# dynalo-dac.net
KiCad netlist of a schematic drawn in EAGLE
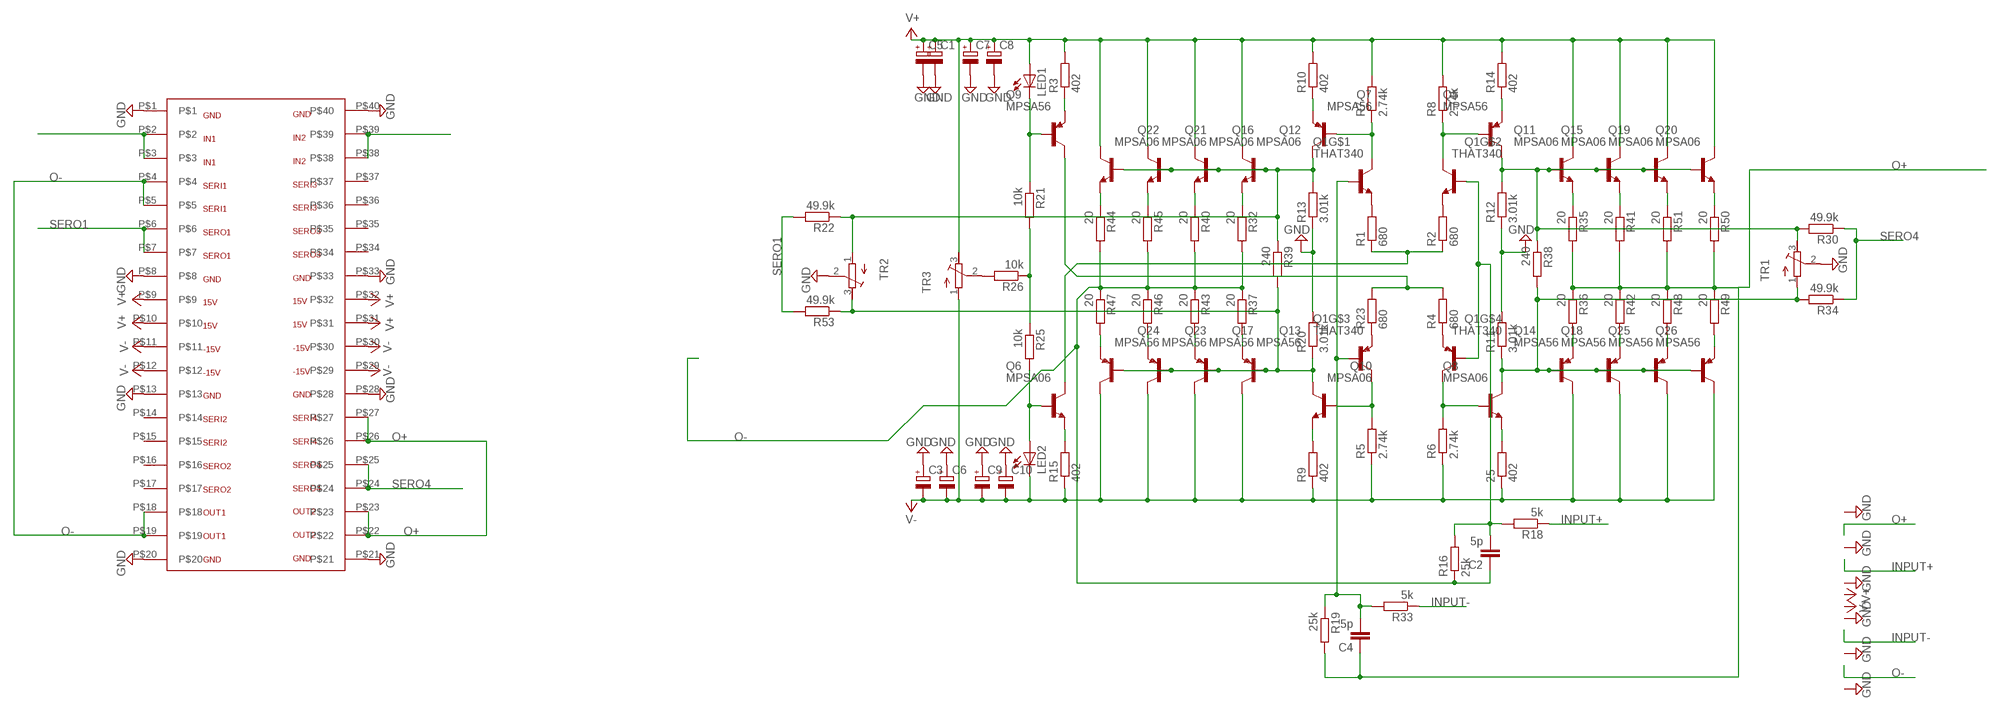
[diagram p0: schematic, sheet 1]

(export (version "E")
  (design (tool "Eeschema 10.0.6"))
  (components
    (comp (ref "25")
      (value "402")
      (footprint "eagle-import:MINI_MELF-0204W")
      (libsource (lib "eagle-import") (part "R-EU_MELF0204W"))
    )
    (comp (ref "C1")
      (value "CPOL-EUSP-CAP-CX")
      (footprint "eagle-import:SP-CAP-CX")
      (libsource (lib "eagle-import") (part "CPOL-EUSP-CAP-CX"))
    )
    (comp (ref "C2")
      (value "5p")
      (footprint "eagle-import:C0805")
      (libsource (lib "eagle-import") (part "C-EUC0805"))
    )
    (comp (ref "C3")
      (value "CPOL-EUSP-CAP-CX")
      (footprint "eagle-import:SP-CAP-CX")
      (libsource (lib "eagle-import") (part "CPOL-EUSP-CAP-CX"))
    )
    (comp (ref "C4")
      (value "5p")
      (footprint "eagle-import:C0805")
      (libsource (lib "eagle-import") (part "C-EUC0805"))
    )
    (comp (ref "C5")
      (value "CPOL-EUSP-CAP-CX")
      (footprint "eagle-import:SP-CAP-CX")
      (libsource (lib "eagle-import") (part "CPOL-EUSP-CAP-CX"))
    )
    (comp (ref "C6")
      (value "CPOL-EUSP-CAP-CX")
      (footprint "eagle-import:SP-CAP-CX")
      (libsource (lib "eagle-import") (part "CPOL-EUSP-CAP-CX"))
    )
    (comp (ref "C7")
      (value "CPOL-EUSP-CAP-CX")
      (footprint "eagle-import:SP-CAP-CX")
      (libsource (lib "eagle-import") (part "CPOL-EUSP-CAP-CX"))
    )
    (comp (ref "C8")
      (value "CPOL-EUSP-CAP-CX")
      (footprint "eagle-import:SP-CAP-CX")
      (libsource (lib "eagle-import") (part "CPOL-EUSP-CAP-CX"))
    )
    (comp (ref "C9")
      (value "CPOL-EUSP-CAP-CX")
      (footprint "eagle-import:SP-CAP-CX")
      (libsource (lib "eagle-import") (part "CPOL-EUSP-CAP-CX"))
    )
    (comp (ref "C10")
      (value "CPOL-EUSP-CAP-CX")
      (footprint "eagle-import:SP-CAP-CX")
      (libsource (lib "eagle-import") (part "CPOL-EUSP-CAP-CX"))
    )
    (comp (ref "LED1")
      (value "LED5MM")
      (footprint "eagle-import:LED5MM")
      (libsource (lib "eagle-import") (part "LED5MM"))
    )
    (comp (ref "LED2")
      (value "LED5MM")
      (footprint "eagle-import:LED5MM")
      (libsource (lib "eagle-import") (part "LED5MM"))
    )
    (comp (ref "Q1")
      (value "THAT340")
      (footprint "eagle-import:DIP254P762X510-14")
      (libsource (lib "eagle-import") (part "THAT340"))
    )
    (comp (ref "Q5")
      (value "MPSA56")
      (footprint "eagle-import:TO92-BCE")
      (libsource (lib "eagle-import") (part "MPSA56"))
    )
    (comp (ref "Q6")
      (value "MPSA06")
      (footprint "eagle-import:TO92-1")
      (libsource (lib "eagle-import") (part "MPSA06"))
    )
    (comp (ref "Q7")
      (value "MPSA56")
      (footprint "eagle-import:TO92-BCE")
      (libsource (lib "eagle-import") (part "MPSA56"))
    )
    (comp (ref "Q8")
      (value "MPSA06")
      (footprint "eagle-import:TO92-1")
      (libsource (lib "eagle-import") (part "MPSA06"))
    )
    (comp (ref "Q9")
      (value "MPSA56")
      (footprint "eagle-import:TO92-BCE")
      (libsource (lib "eagle-import") (part "MPSA56"))
    )
    (comp (ref "Q10")
      (value "MPSA06")
      (footprint "eagle-import:TO92-1")
      (libsource (lib "eagle-import") (part "MPSA06"))
    )
    (comp (ref "Q11")
      (value "MPSA06")
      (footprint "eagle-import:TO92-1")
      (libsource (lib "eagle-import") (part "MPSA06"))
    )
    (comp (ref "Q12")
      (value "MPSA06")
      (footprint "eagle-import:TO92-1")
      (libsource (lib "eagle-import") (part "MPSA06"))
    )
    (comp (ref "Q13")
      (value "MPSA56")
      (footprint "eagle-import:TO92-BCE")
      (libsource (lib "eagle-import") (part "MPSA56"))
    )
    (comp (ref "Q14")
      (value "MPSA56")
      (footprint "eagle-import:TO92-BCE")
      (libsource (lib "eagle-import") (part "MPSA56"))
    )
    (comp (ref "Q15")
      (value "MPSA06")
      (footprint "eagle-import:TO92-1")
      (libsource (lib "eagle-import") (part "MPSA06"))
    )
    (comp (ref "Q16")
      (value "MPSA06")
      (footprint "eagle-import:TO92-1")
      (libsource (lib "eagle-import") (part "MPSA06"))
    )
    (comp (ref "Q17")
      (value "MPSA56")
      (footprint "eagle-import:TO92-BCE")
      (libsource (lib "eagle-import") (part "MPSA56"))
    )
    (comp (ref "Q18")
      (value "MPSA56")
      (footprint "eagle-import:TO92-BCE")
      (libsource (lib "eagle-import") (part "MPSA56"))
    )
    (comp (ref "Q19")
      (value "MPSA06")
      (footprint "eagle-import:TO92-1")
      (libsource (lib "eagle-import") (part "MPSA06"))
    )
    (comp (ref "Q20")
      (value "MPSA06")
      (footprint "eagle-import:TO92-1")
      (libsource (lib "eagle-import") (part "MPSA06"))
    )
    (comp (ref "Q21")
      (value "MPSA06")
      (footprint "eagle-import:TO92-1")
      (libsource (lib "eagle-import") (part "MPSA06"))
    )
    (comp (ref "Q22")
      (value "MPSA06")
      (footprint "eagle-import:TO92-1")
      (libsource (lib "eagle-import") (part "MPSA06"))
    )
    (comp (ref "Q23")
      (value "MPSA56")
      (footprint "eagle-import:TO92-BCE")
      (libsource (lib "eagle-import") (part "MPSA56"))
    )
    (comp (ref "Q24")
      (value "MPSA56")
      (footprint "eagle-import:TO92-BCE")
      (libsource (lib "eagle-import") (part "MPSA56"))
    )
    (comp (ref "Q25")
      (value "MPSA56")
      (footprint "eagle-import:TO92-BCE")
      (libsource (lib "eagle-import") (part "MPSA56"))
    )
    (comp (ref "Q26")
      (value "MPSA56")
      (footprint "eagle-import:TO92-BCE")
      (libsource (lib "eagle-import") (part "MPSA56"))
    )
    (comp (ref "R1")
      (value "680")
      (footprint "eagle-import:MINI_MELF-0204W")
      (libsource (lib "eagle-import") (part "R-EU_MELF0204W"))
    )
    (comp (ref "R2")
      (value "680")
      (footprint "eagle-import:MINI_MELF-0204W")
      (libsource (lib "eagle-import") (part "R-EU_MELF0204W"))
    )
    (comp (ref "R3")
      (value "402")
      (footprint "eagle-import:MINI_MELF-0204W")
      (libsource (lib "eagle-import") (part "R-EU_MELF0204W"))
    )
    (comp (ref "R4")
      (value "680")
      (footprint "eagle-import:MINI_MELF-0204W")
      (libsource (lib "eagle-import") (part "R-EU_MELF0204W"))
    )
    (comp (ref "R5")
      (value "2.74k")
      (footprint "eagle-import:MINI_MELF-0204W")
      (libsource (lib "eagle-import") (part "R-EU_MELF0204W"))
    )
    (comp (ref "R6")
      (value "2.74k")
      (footprint "eagle-import:MINI_MELF-0204W")
      (libsource (lib "eagle-import") (part "R-EU_MELF0204W"))
    )
    (comp (ref "R7")
      (value "2.74k")
      (footprint "eagle-import:MINI_MELF-0204W")
      (libsource (lib "eagle-import") (part "R-EU_MELF0204W"))
    )
    (comp (ref "R8")
      (value "2.74k")
      (footprint "eagle-import:MINI_MELF-0204W")
      (libsource (lib "eagle-import") (part "R-EU_MELF0204W"))
    )
    (comp (ref "R9")
      (value "402")
      (footprint "eagle-import:MINI_MELF-0204W")
      (libsource (lib "eagle-import") (part "R-EU_MELF0204W"))
    )
    (comp (ref "R10")
      (value "402")
      (footprint "eagle-import:MINI_MELF-0204W")
      (libsource (lib "eagle-import") (part "R-EU_MELF0204W"))
    )
    (comp (ref "R11")
      (value "3.01k")
      (footprint "eagle-import:MINI_MELF-0204W")
      (libsource (lib "eagle-import") (part "R-EU_MELF0204W"))
    )
    (comp (ref "R12")
      (value "3.01k")
      (footprint "eagle-import:MINI_MELF-0204W")
      (libsource (lib "eagle-import") (part "R-EU_MELF0204W"))
    )
    (comp (ref "R13")
      (value "3.01k")
      (footprint "eagle-import:MINI_MELF-0204W")
      (libsource (lib "eagle-import") (part "R-EU_MELF0204W"))
    )
    (comp (ref "R14")
      (value "402")
      (footprint "eagle-import:MINI_MELF-0204W")
      (libsource (lib "eagle-import") (part "R-EU_MELF0204W"))
    )
    (comp (ref "R15")
      (value "402")
      (footprint "eagle-import:MINI_MELF-0204W")
      (libsource (lib "eagle-import") (part "R-EU_MELF0204W"))
    )
    (comp (ref "R16")
      (value "25k")
      (footprint "eagle-import:MINI_MELF-0204W")
      (libsource (lib "eagle-import") (part "R-EU_MELF0204W"))
    )
    (comp (ref "R18")
      (value "5k")
      (footprint "eagle-import:MINI_MELF-0204W")
      (libsource (lib "eagle-import") (part "R-EU_MELF0204W"))
    )
    (comp (ref "R19")
      (value "25k")
      (footprint "eagle-import:MINI_MELF-0204W")
      (libsource (lib "eagle-import") (part "R-EU_MELF0204W"))
    )
    (comp (ref "R20")
      (value "3.01k")
      (footprint "eagle-import:MINI_MELF-0204W")
      (libsource (lib "eagle-import") (part "R-EU_MELF0204W"))
    )
    (comp (ref "R21")
      (value "10k")
      (footprint "eagle-import:MINI_MELF-0204W")
      (libsource (lib "eagle-import") (part "R-EU_MELF0204W"))
    )
    (comp (ref "R22")
      (value "49.9k")
      (footprint "eagle-import:MINI_MELF-0204W")
      (libsource (lib "eagle-import") (part "R-EU_MELF0204W"))
    )
    (comp (ref "R23")
      (value "680")
      (footprint "eagle-import:MINI_MELF-0204W")
      (libsource (lib "eagle-import") (part "R-EU_MELF0204W"))
    )
    (comp (ref "R25")
      (value "10k")
      (footprint "eagle-import:MINI_MELF-0204W")
      (libsource (lib "eagle-import") (part "R-EU_MELF0204W"))
    )
    (comp (ref "R26")
      (value "10k")
      (footprint "eagle-import:MINI_MELF-0204W")
      (libsource (lib "eagle-import") (part "R-EU_MELF0204W"))
    )
    (comp (ref "R30")
      (value "49.9k")
      (footprint "eagle-import:MINI_MELF-0204W")
      (libsource (lib "eagle-import") (part "R-EU_MELF0204W"))
    )
    (comp (ref "R32")
      (value "20")
      (footprint "eagle-import:MINI_MELF-0204W")
      (libsource (lib "eagle-import") (part "R-EU_MELF0204W"))
    )
    (comp (ref "R33")
      (value "5k")
      (footprint "eagle-import:MINI_MELF-0204W")
      (libsource (lib "eagle-import") (part "R-EU_MELF0204W"))
    )
    (comp (ref "R34")
      (value "49.9k")
      (footprint "eagle-import:MINI_MELF-0204W")
      (libsource (lib "eagle-import") (part "R-EU_MELF0204W"))
    )
    (comp (ref "R35")
      (value "20")
      (footprint "eagle-import:MINI_MELF-0204W")
      (libsource (lib "eagle-import") (part "R-EU_MELF0204W"))
    )
    (comp (ref "R36")
      (value "20")
      (footprint "eagle-import:MINI_MELF-0204W")
      (libsource (lib "eagle-import") (part "R-EU_MELF0204W"))
    )
    (comp (ref "R37")
      (value "20")
      (footprint "eagle-import:MINI_MELF-0204W")
      (libsource (lib "eagle-import") (part "R-EU_MELF0204W"))
    )
    (comp (ref "R38")
      (value "240")
      (footprint "eagle-import:MINI_MELF-0204W")
      (libsource (lib "eagle-import") (part "R-EU_MELF0204W"))
    )
    (comp (ref "R39")
      (value "240")
      (footprint "eagle-import:MINI_MELF-0204W")
      (libsource (lib "eagle-import") (part "R-EU_MELF0204W"))
    )
    (comp (ref "R40")
      (value "20")
      (footprint "eagle-import:MINI_MELF-0204W")
      (libsource (lib "eagle-import") (part "R-EU_MELF0204W"))
    )
    (comp (ref "R41")
      (value "20")
      (footprint "eagle-import:MINI_MELF-0204W")
      (libsource (lib "eagle-import") (part "R-EU_MELF0204W"))
    )
    (comp (ref "R42")
      (value "20")
      (footprint "eagle-import:MINI_MELF-0204W")
      (libsource (lib "eagle-import") (part "R-EU_MELF0204W"))
    )
    (comp (ref "R43")
      (value "20")
      (footprint "eagle-import:MINI_MELF-0204W")
      (libsource (lib "eagle-import") (part "R-EU_MELF0204W"))
    )
    (comp (ref "R44")
      (value "20")
      (footprint "eagle-import:MINI_MELF-0204W")
      (libsource (lib "eagle-import") (part "R-EU_MELF0204W"))
    )
    (comp (ref "R45")
      (value "20")
      (footprint "eagle-import:MINI_MELF-0204W")
      (libsource (lib "eagle-import") (part "R-EU_MELF0204W"))
    )
    (comp (ref "R46")
      (value "20")
      (footprint "eagle-import:MINI_MELF-0204W")
      (libsource (lib "eagle-import") (part "R-EU_MELF0204W"))
    )
    (comp (ref "R47")
      (value "20")
      (footprint "eagle-import:MINI_MELF-0204W")
      (libsource (lib "eagle-import") (part "R-EU_MELF0204W"))
    )
    (comp (ref "R48")
      (value "20")
      (footprint "eagle-import:MINI_MELF-0204W")
      (libsource (lib "eagle-import") (part "R-EU_MELF0204W"))
    )
    (comp (ref "R49")
      (value "20")
      (footprint "eagle-import:MINI_MELF-0204W")
      (libsource (lib "eagle-import") (part "R-EU_MELF0204W"))
    )
    (comp (ref "R50")
      (value "20")
      (footprint "eagle-import:MINI_MELF-0204W")
      (libsource (lib "eagle-import") (part "R-EU_MELF0204W"))
    )
    (comp (ref "R51")
      (value "20")
      (footprint "eagle-import:MINI_MELF-0204W")
      (libsource (lib "eagle-import") (part "R-EU_MELF0204W"))
    )
    (comp (ref "R53")
      (value "49.9k")
      (footprint "eagle-import:MINI_MELF-0204W")
      (libsource (lib "eagle-import") (part "R-EU_MELF0204W"))
    )
    (comp (ref "TR1")
      (value "R-TRIMM3296W")
      (footprint "eagle-import:RTRIM3296W")
      (libsource (lib "eagle-import") (part "R-TRIMM3296W"))
    )
    (comp (ref "TR2")
      (value "R-TRIMM3296W")
      (footprint "eagle-import:RTRIM3296W")
      (libsource (lib "eagle-import") (part "R-TRIMM3296W"))
    )
    (comp (ref "TR3")
      (value "R-TRIMM3296W")
      (footprint "eagle-import:RTRIM3296W")
      (libsource (lib "eagle-import") (part "R-TRIMM3296W"))
    )
    (comp (ref "U$1")
      (value "VDACA")
      (footprint "eagle-import:VDACA")
      (libsource (lib "eagle-import") (part "VDACA"))
    )
  )
  (nets
    (net (code "1") (name "/INPUT+") (class "Default")
      (node (ref "R18") (pin "1") (pinfunction "1_1") (pintype "passive"))
      (node (ref "U$1") (pin "P$38") (pinfunction "P$38_P$38") (pintype "bidirectional"))
      (node (ref "U$1") (pin "P$39") (pinfunction "P$39_P$39") (pintype "bidirectional"))
    )
    (net (code "2") (name "/INPUT-") (class "Default")
      (node (ref "R33") (pin "1") (pinfunction "1_1") (pintype "passive"))
      (node (ref "U$1") (pin "P$2") (pinfunction "P$2_P$2") (pintype "bidirectional"))
      (node (ref "U$1") (pin "P$3") (pinfunction "P$3_P$3") (pintype "bidirectional"))
    )
    (net (code "3") (name "/O+") (class "Default")
      (node (ref "C4") (pin "1") (pinfunction "1_1") (pintype "passive"))
      (node (ref "R19") (pin "2") (pinfunction "2_2") (pintype "passive"))
      (node (ref "R35") (pin "2") (pinfunction "2_2") (pintype "passive"))
      (node (ref "R36") (pin "1") (pinfunction "1_1") (pintype "passive"))
      (node (ref "R41") (pin "2") (pinfunction "2_2") (pintype "passive"))
      (node (ref "R42") (pin "1") (pinfunction "1_1") (pintype "passive"))
      (node (ref "R48") (pin "1") (pinfunction "1_1") (pintype "passive"))
      (node (ref "R49") (pin "1") (pinfunction "1_1") (pintype "passive"))
      (node (ref "R50") (pin "2") (pinfunction "2_2") (pintype "passive"))
      (node (ref "R51") (pin "2") (pinfunction "2_2") (pintype "passive"))
      (node (ref "U$1") (pin "P$22") (pinfunction "P$22_P$22") (pintype "bidirectional"))
      (node (ref "U$1") (pin "P$23") (pinfunction "P$23_P$23") (pintype "bidirectional"))
      (node (ref "U$1") (pin "P$26") (pinfunction "P$26_P$26") (pintype "bidirectional"))
      (node (ref "U$1") (pin "P$27") (pinfunction "P$27_P$27") (pintype "bidirectional"))
    )
    (net (code "4") (name "/O-") (class "Default")
      (node (ref "C2") (pin "1") (pinfunction "1_1") (pintype "passive"))
      (node (ref "R16") (pin "1") (pinfunction "1_1") (pintype "passive"))
      (node (ref "R32") (pin "2") (pinfunction "2_2") (pintype "passive"))
      (node (ref "R37") (pin "1") (pinfunction "1_1") (pintype "passive"))
      (node (ref "R40") (pin "2") (pinfunction "2_2") (pintype "passive"))
      (node (ref "R43") (pin "1") (pinfunction "1_1") (pintype "passive"))
      (node (ref "R44") (pin "2") (pinfunction "2_2") (pintype "passive"))
      (node (ref "R45") (pin "2") (pinfunction "2_2") (pintype "passive"))
      (node (ref "R46") (pin "1") (pinfunction "1_1") (pintype "passive"))
      (node (ref "R47") (pin "1") (pinfunction "1_1") (pintype "passive"))
      (node (ref "U$1") (pin "P$18") (pinfunction "P$18_P$18") (pintype "bidirectional"))
      (node (ref "U$1") (pin "P$19") (pinfunction "P$19_P$19") (pintype "bidirectional"))
      (node (ref "U$1") (pin "P$4") (pinfunction "P$4_P$4") (pintype "bidirectional"))
      (node (ref "U$1") (pin "P$5") (pinfunction "P$5_P$5") (pintype "bidirectional"))
    )
    (net (code "5") (name "/SERO1") (class "Default")
      (node (ref "R22") (pin "2") (pinfunction "2_2") (pintype "passive"))
      (node (ref "R53") (pin "2") (pinfunction "2_2") (pintype "passive"))
      (node (ref "U$1") (pin "P$6") (pinfunction "P$6_P$6") (pintype "bidirectional"))
      (node (ref "U$1") (pin "P$7") (pinfunction "P$7_P$7") (pintype "bidirectional"))
    )
    (net (code "6") (name "/SERO4") (class "Default")
      (node (ref "R30") (pin "1") (pinfunction "1_1") (pintype "passive"))
      (node (ref "R34") (pin "1") (pinfunction "1_1") (pintype "passive"))
      (node (ref "U$1") (pin "P$24") (pinfunction "P$24_P$24") (pintype "bidirectional"))
      (node (ref "U$1") (pin "P$25") (pinfunction "P$25_P$25") (pintype "bidirectional"))
    )
    (net (code "7") (name "GND") (class "Default")
      (node (ref "C1") (pin "-") (pinfunction "-_-") (pintype "passive"))
      (node (ref "C10") (pin "+") (pinfunction "+_+") (pintype "passive"))
      (node (ref "C3") (pin "+") (pinfunction "+_+") (pintype "passive"))
      (node (ref "C5") (pin "-") (pinfunction "-_-") (pintype "passive"))
      (node (ref "C6") (pin "+") (pinfunction "+_+") (pintype "passive"))
      (node (ref "C7") (pin "-") (pinfunction "-_-") (pintype "passive"))
      (node (ref "C8") (pin "-") (pinfunction "-_-") (pintype "passive"))
      (node (ref "C9") (pin "+") (pinfunction "+_+") (pintype "passive"))
      (node (ref "R11") (pin "2") (pinfunction "2_2") (pintype "passive"))
      (node (ref "R12") (pin "1") (pinfunction "1_1") (pintype "passive"))
      (node (ref "R13") (pin "1") (pinfunction "1_1") (pintype "passive"))
      (node (ref "R20") (pin "2") (pinfunction "2_2") (pintype "passive"))
      (node (ref "TR1") (pin "2") (pinfunction "S_2") (pintype "passive"))
      (node (ref "TR2") (pin "2") (pinfunction "S_2") (pintype "passive"))
      (node (ref "U$1") (pin "P$1") (pinfunction "P$1_P$1") (pintype "bidirectional"))
      (node (ref "U$1") (pin "P$13") (pinfunction "P$13_P$13") (pintype "bidirectional"))
      (node (ref "U$1") (pin "P$20") (pinfunction "P$20_P$20") (pintype "bidirectional"))
      (node (ref "U$1") (pin "P$21") (pinfunction "P$21_P$21") (pintype "bidirectional"))
      (node (ref "U$1") (pin "P$28") (pinfunction "P$28_P$28") (pintype "bidirectional"))
      (node (ref "U$1") (pin "P$33") (pinfunction "P$33_P$33") (pintype "bidirectional"))
      (node (ref "U$1") (pin "P$40") (pinfunction "P$40_P$40") (pintype "bidirectional"))
      (node (ref "U$1") (pin "P$8") (pinfunction "P$8_P$8") (pintype "bidirectional"))
    )
    (net (code "8") (name "Net-(LED1-C)") (class "Default")
      (node (ref "LED1") (pin "K") (pinfunction "C_K") (pintype "passive"))
      (node (ref "Q9") (pin "C") (pinfunction "B_C") (pintype "passive"))
      (node (ref "R21") (pin "1") (pinfunction "1_1") (pintype "passive"))
    )
    (net (code "9") (name "Net-(Q1A-B)") (class "Default")
      (node (ref "C4") (pin "2") (pinfunction "2_2") (pintype "passive"))
      (node (ref "Q1") (pin "2") (pinfunction "B_2") (pintype "passive"))
      (node (ref "Q1") (pin "6") (pinfunction "B_6") (pintype "passive"))
      (node (ref "R19") (pin "1") (pinfunction "1_1") (pintype "passive"))
      (node (ref "R33") (pin "2") (pinfunction "2_2") (pintype "passive"))
    )
    (net (code "10") (name "Net-(Q1A-C)") (class "Default")
      (node (ref "Q1") (pin "1") (pinfunction "C_1") (pintype "passive"))
      (node (ref "Q7") (pin "C") (pinfunction "B_C") (pintype "passive"))
      (node (ref "R7") (pin "1") (pinfunction "1_1") (pintype "passive"))
    )
    (net (code "11") (name "Net-(Q1A-E)") (class "Default")
      (node (ref "Q1") (pin "3") (pinfunction "E_3") (pintype "passive"))
      (node (ref "R1") (pin "2") (pinfunction "2_2") (pintype "passive"))
    )
    (net (code "12") (name "Net-(Q1B-B)") (class "Default")
      (node (ref "C2") (pin "2") (pinfunction "2_2") (pintype "passive"))
      (node (ref "Q1") (pin "13") (pinfunction "B_13") (pintype "passive"))
      (node (ref "Q1") (pin "9") (pinfunction "B_9") (pintype "passive"))
      (node (ref "R16") (pin "2") (pinfunction "2_2") (pintype "passive"))
      (node (ref "R18") (pin "2") (pinfunction "2_2") (pintype "passive"))
    )
    (net (code "13") (name "Net-(Q1B-C)") (class "Default")
      (node (ref "Q1") (pin "14") (pinfunction "C_14") (pintype "passive"))
      (node (ref "Q5") (pin "C") (pinfunction "B_C") (pintype "passive"))
      (node (ref "R8") (pin "1") (pinfunction "1_1") (pintype "passive"))
    )
    (net (code "14") (name "Net-(Q1B-E)") (class "Default")
      (node (ref "Q1") (pin "12") (pinfunction "E_12") (pintype "passive"))
      (node (ref "R2") (pin "2") (pinfunction "2_2") (pintype "passive"))
    )
    (net (code "15") (name "Net-(Q1C-E)") (class "Default")
      (node (ref "Q1") (pin "5") (pinfunction "E_5") (pintype "passive"))
      (node (ref "R23") (pin "1") (pinfunction "1_1") (pintype "passive"))
    )
    (net (code "16") (name "Net-(Q1D-C)") (class "Default")
      (node (ref "Q1") (pin "8") (pinfunction "C_8") (pintype "passive"))
      (node (ref "Q8") (pin "2") (pinfunction "B_2") (pintype "passive"))
      (node (ref "R6") (pin "2") (pinfunction "2_2") (pintype "passive"))
    )
    (net (code "17") (name "Net-(Q1D-E)") (class "Default")
      (node (ref "Q1") (pin "10") (pinfunction "E_10") (pintype "passive"))
      (node (ref "R4") (pin "1") (pinfunction "1_1") (pintype "passive"))
    )
    (net (code "18") (name "Net-(Q5-PadE)") (class "Default")
      (node (ref "Q5") (pin "E") (pinfunction "E_E") (pintype "passive"))
      (node (ref "R14") (pin "1") (pinfunction "1_1") (pintype "passive"))
    )
    (net (code "19") (name "Net-(Q6-B)") (class "Default")
      (node (ref "LED2") (pin "A") (pinfunction "A_A") (pintype "passive"))
      (node (ref "Q6") (pin "2") (pinfunction "B_2") (pintype "passive"))
      (node (ref "R25") (pin "2") (pinfunction "2_2") (pintype "passive"))
    )
    (net (code "20") (name "Net-(Q6-C)") (class "Default")
      (node (ref "Q6") (pin "3") (pinfunction "C_3") (pintype "passive"))
      (node (ref "R1") (pin "1") (pinfunction "1_1") (pintype "passive"))
      (node (ref "R2") (pin "1") (pinfunction "1_1") (pintype "passive"))
    )
    (net (code "21") (name "Net-(Q6-E)") (class "Default")
      (node (ref "Q6") (pin "1") (pinfunction "E_1") (pintype "passive"))
      (node (ref "R15") (pin "2") (pinfunction "2_2") (pintype "passive"))
    )
    (net (code "22") (name "Net-(Q7-PadE)") (class "Default")
      (node (ref "Q7") (pin "E") (pinfunction "E_E") (pintype "passive"))
      (node (ref "R10") (pin "1") (pinfunction "1_1") (pintype "passive"))
    )
    (net (code "23") (name "Net-(Q8-E)") (class "Default")
      (node (ref "25") (pin "2") (pinfunction "2_2") (pintype "passive"))
      (node (ref "Q8") (pin "1") (pinfunction "E_1") (pintype "passive"))
    )
    (net (code "24") (name "Net-(Q9-C)") (class "Default")
      (node (ref "Q9") (pin "B") (pinfunction "C_B") (pintype "passive"))
      (node (ref "R23") (pin "2") (pinfunction "2_2") (pintype "passive"))
      (node (ref "R4") (pin "2") (pinfunction "2_2") (pintype "passive"))
    )
    (net (code "25") (name "Net-(Q9-PadE)") (class "Default")
      (node (ref "Q9") (pin "E") (pinfunction "E_E") (pintype "passive"))
      (node (ref "R3") (pin "1") (pinfunction "1_1") (pintype "passive"))
    )
    (net (code "26") (name "Net-(Q10-B)") (class "Default")
      (node (ref "Q1") (pin "7") (pinfunction "C_7") (pintype "passive"))
      (node (ref "Q10") (pin "2") (pinfunction "B_2") (pintype "passive"))
      (node (ref "R5") (pin "2") (pinfunction "2_2") (pintype "passive"))
    )
    (net (code "27") (name "Net-(Q10-C)") (class "Default")
      (node (ref "Q10") (pin "3") (pinfunction "C_3") (pintype "passive"))
      (node (ref "Q13") (pin "C") (pinfunction "B_C") (pintype "passive"))
      (node (ref "Q17") (pin "C") (pinfunction "B_C") (pintype "passive"))
      (node (ref "Q23") (pin "C") (pinfunction "B_C") (pintype "passive"))
      (node (ref "Q24") (pin "C") (pinfunction "B_C") (pintype "passive"))
      (node (ref "R20") (pin "1") (pinfunction "1_1") (pintype "passive"))
      (node (ref "R39") (pin "2") (pinfunction "2_2") (pintype "passive"))
      (node (ref "R53") (pin "1") (pinfunction "1_1") (pintype "passive"))
      (node (ref "TR2") (pin "3") (pinfunction "E_3") (pintype "passive"))
    )
    (net (code "28") (name "Net-(Q10-E)") (class "Default")
      (node (ref "Q10") (pin "1") (pinfunction "E_1") (pintype "passive"))
      (node (ref "R9") (pin "2") (pinfunction "2_2") (pintype "passive"))
    )
    (net (code "29") (name "Net-(Q11-B)") (class "Default")
      (node (ref "Q11") (pin "2") (pinfunction "B_2") (pintype "passive"))
      (node (ref "Q15") (pin "2") (pinfunction "B_2") (pintype "passive"))
      (node (ref "Q19") (pin "2") (pinfunction "B_2") (pintype "passive"))
      (node (ref "Q20") (pin "2") (pinfunction "B_2") (pintype "passive"))
      (node (ref "Q5") (pin "B") (pinfunction "C_B") (pintype "passive"))
      (node (ref "R12") (pin "2") (pinfunction "2_2") (pintype "passive"))
      (node (ref "R30") (pin "2") (pinfunction "2_2") (pintype "passive"))
      (node (ref "R38") (pin "1") (pinfunction "1_1") (pintype "passive"))
      (node (ref "TR1") (pin "3") (pinfunction "E_3") (pintype "passive"))
    )
    (net (code "30") (name "Net-(Q11-E)") (class "Default")
      (node (ref "Q11") (pin "1") (pinfunction "E_1") (pintype "passive"))
      (node (ref "R35") (pin "1") (pinfunction "1_1") (pintype "passive"))
    )
    (net (code "31") (name "Net-(Q12-B)") (class "Default")
      (node (ref "Q12") (pin "2") (pinfunction "B_2") (pintype "passive"))
      (node (ref "Q16") (pin "2") (pinfunction "B_2") (pintype "passive"))
      (node (ref "Q21") (pin "2") (pinfunction "B_2") (pintype "passive"))
      (node (ref "Q22") (pin "2") (pinfunction "B_2") (pintype "passive"))
      (node (ref "Q7") (pin "B") (pinfunction "C_B") (pintype "passive"))
      (node (ref "R13") (pin "2") (pinfunction "2_2") (pintype "passive"))
      (node (ref "R22") (pin "1") (pinfunction "1_1") (pintype "passive"))
      (node (ref "R39") (pin "1") (pinfunction "1_1") (pintype "passive"))
      (node (ref "TR2") (pin "1") (pinfunction "A_1") (pintype "passive"))
    )
    (net (code "32") (name "Net-(Q12-E)") (class "Default")
      (node (ref "Q12") (pin "1") (pinfunction "E_1") (pintype "passive"))
      (node (ref "R32") (pin "1") (pinfunction "1_1") (pintype "passive"))
    )
    (net (code "33") (name "Net-(Q13-PadE)") (class "Default")
      (node (ref "Q13") (pin "E") (pinfunction "E_E") (pintype "passive"))
      (node (ref "R37") (pin "2") (pinfunction "2_2") (pintype "passive"))
    )
    (net (code "34") (name "Net-(Q14-B)") (class "Default")
      (node (ref "Q14") (pin "C") (pinfunction "B_C") (pintype "passive"))
      (node (ref "Q18") (pin "C") (pinfunction "B_C") (pintype "passive"))
      (node (ref "Q25") (pin "C") (pinfunction "B_C") (pintype "passive"))
      (node (ref "Q26") (pin "C") (pinfunction "B_C") (pintype "passive"))
      (node (ref "Q8") (pin "3") (pinfunction "C_3") (pintype "passive"))
      (node (ref "R11") (pin "1") (pinfunction "1_1") (pintype "passive"))
      (node (ref "R34") (pin "2") (pinfunction "2_2") (pintype "passive"))
      (node (ref "R38") (pin "2") (pinfunction "2_2") (pintype "passive"))
      (node (ref "TR1") (pin "1") (pinfunction "A_1") (pintype "passive"))
    )
    (net (code "35") (name "Net-(Q14-PadE)") (class "Default")
      (node (ref "Q14") (pin "E") (pinfunction "E_E") (pintype "passive"))
      (node (ref "R36") (pin "2") (pinfunction "2_2") (pintype "passive"))
    )
    (net (code "36") (name "Net-(Q15-E)") (class "Default")
      (node (ref "Q15") (pin "1") (pinfunction "E_1") (pintype "passive"))
      (node (ref "R41") (pin "1") (pinfunction "1_1") (pintype "passive"))
    )
    (net (code "37") (name "Net-(Q16-E)") (class "Default")
      (node (ref "Q16") (pin "1") (pinfunction "E_1") (pintype "passive"))
      (node (ref "R40") (pin "1") (pinfunction "1_1") (pintype "passive"))
    )
    (net (code "38") (name "Net-(Q17-PadE)") (class "Default")
      (node (ref "Q17") (pin "E") (pinfunction "E_E") (pintype "passive"))
      (node (ref "R43") (pin "2") (pinfunction "2_2") (pintype "passive"))
    )
    (net (code "39") (name "Net-(Q18-PadE)") (class "Default")
      (node (ref "Q18") (pin "E") (pinfunction "E_E") (pintype "passive"))
      (node (ref "R42") (pin "2") (pinfunction "2_2") (pintype "passive"))
    )
    (net (code "40") (name "Net-(Q19-E)") (class "Default")
      (node (ref "Q19") (pin "1") (pinfunction "E_1") (pintype "passive"))
      (node (ref "R51") (pin "1") (pinfunction "1_1") (pintype "passive"))
    )
    (net (code "41") (name "Net-(Q20-E)") (class "Default")
      (node (ref "Q20") (pin "1") (pinfunction "E_1") (pintype "passive"))
      (node (ref "R50") (pin "1") (pinfunction "1_1") (pintype "passive"))
    )
    (net (code "42") (name "Net-(Q21-E)") (class "Default")
      (node (ref "Q21") (pin "1") (pinfunction "E_1") (pintype "passive"))
      (node (ref "R45") (pin "1") (pinfunction "1_1") (pintype "passive"))
    )
    (net (code "43") (name "Net-(Q22-E)") (class "Default")
      (node (ref "Q22") (pin "1") (pinfunction "E_1") (pintype "passive"))
      (node (ref "R44") (pin "1") (pinfunction "1_1") (pintype "passive"))
    )
    (net (code "44") (name "Net-(Q23-PadE)") (class "Default")
      (node (ref "Q23") (pin "E") (pinfunction "E_E") (pintype "passive"))
      (node (ref "R46") (pin "2") (pinfunction "2_2") (pintype "passive"))
    )
    (net (code "45") (name "Net-(Q24-PadE)") (class "Default")
      (node (ref "Q24") (pin "E") (pinfunction "E_E") (pintype "passive"))
      (node (ref "R47") (pin "2") (pinfunction "2_2") (pintype "passive"))
    )
    (net (code "46") (name "Net-(Q25-PadE)") (class "Default")
      (node (ref "Q25") (pin "E") (pinfunction "E_E") (pintype "passive"))
      (node (ref "R48") (pin "2") (pinfunction "2_2") (pintype "passive"))
    )
    (net (code "47") (name "Net-(Q26-PadE)") (class "Default")
      (node (ref "Q26") (pin "E") (pinfunction "E_E") (pintype "passive"))
      (node (ref "R49") (pin "2") (pinfunction "2_2") (pintype "passive"))
    )
    (net (code "48") (name "Net-(R21-Pad2)") (class "Default")
      (node (ref "R21") (pin "2") (pinfunction "2_2") (pintype "passive"))
      (node (ref "R25") (pin "1") (pinfunction "1_1") (pintype "passive"))
      (node (ref "R26") (pin "1") (pinfunction "1_1") (pintype "passive"))
    )
    (net (code "49") (name "Net-(TR3-S)") (class "Default")
      (node (ref "R26") (pin "2") (pinfunction "2_2") (pintype "passive"))
      (node (ref "TR3") (pin "2") (pinfunction "S_2") (pintype "passive"))
    )
    (net (code "50") (name "V+") (class "Default")
      (node (ref "C1") (pin "+") (pinfunction "+_+") (pintype "passive"))
      (node (ref "C5") (pin "+") (pinfunction "+_+") (pintype "passive"))
      (node (ref "C7") (pin "+") (pinfunction "+_+") (pintype "passive"))
      (node (ref "C8") (pin "+") (pinfunction "+_+") (pintype "passive"))
      (node (ref "LED1") (pin "A") (pinfunction "A_A") (pintype "passive"))
      (node (ref "Q11") (pin "3") (pinfunction "C_3") (pintype "passive"))
      (node (ref "Q12") (pin "3") (pinfunction "C_3") (pintype "passive"))
      (node (ref "Q15") (pin "3") (pinfunction "C_3") (pintype "passive"))
      (node (ref "Q16") (pin "3") (pinfunction "C_3") (pintype "passive"))
      (node (ref "Q19") (pin "3") (pinfunction "C_3") (pintype "passive"))
      (node (ref "Q20") (pin "3") (pinfunction "C_3") (pintype "passive"))
      (node (ref "Q21") (pin "3") (pinfunction "C_3") (pintype "passive"))
      (node (ref "Q22") (pin "3") (pinfunction "C_3") (pintype "passive"))
      (node (ref "R10") (pin "2") (pinfunction "2_2") (pintype "passive"))
      (node (ref "R14") (pin "2") (pinfunction "2_2") (pintype "passive"))
      (node (ref "R3") (pin "2") (pinfunction "2_2") (pintype "passive"))
      (node (ref "R7") (pin "2") (pinfunction "2_2") (pintype "passive"))
      (node (ref "R8") (pin "2") (pinfunction "2_2") (pintype "passive"))
      (node (ref "TR3") (pin "3") (pinfunction "E_3") (pintype "passive"))
      (node (ref "U$1") (pin "P$10") (pinfunction "P$10_P$10") (pintype "bidirectional"))
      (node (ref "U$1") (pin "P$31") (pinfunction "P$31_P$31") (pintype "bidirectional"))
      (node (ref "U$1") (pin "P$32") (pinfunction "P$32_P$32") (pintype "bidirectional"))
      (node (ref "U$1") (pin "P$9") (pinfunction "P$9_P$9") (pintype "bidirectional"))
    )
    (net (code "51") (name "V-") (class "Default")
      (node (ref "25") (pin "1") (pinfunction "1_1") (pintype "passive"))
      (node (ref "C10") (pin "-") (pinfunction "-_-") (pintype "passive"))
      (node (ref "C3") (pin "-") (pinfunction "-_-") (pintype "passive"))
      (node (ref "C6") (pin "-") (pinfunction "-_-") (pintype "passive"))
      (node (ref "C9") (pin "-") (pinfunction "-_-") (pintype "passive"))
      (node (ref "LED2") (pin "K") (pinfunction "C_K") (pintype "passive"))
      (node (ref "Q13") (pin "B") (pinfunction "C_B") (pintype "passive"))
      (node (ref "Q14") (pin "B") (pinfunction "C_B") (pintype "passive"))
      (node (ref "Q17") (pin "B") (pinfunction "C_B") (pintype "passive"))
      (node (ref "Q18") (pin "B") (pinfunction "C_B") (pintype "passive"))
      (node (ref "Q23") (pin "B") (pinfunction "C_B") (pintype "passive"))
      (node (ref "Q24") (pin "B") (pinfunction "C_B") (pintype "passive"))
      (node (ref "Q25") (pin "B") (pinfunction "C_B") (pintype "passive"))
      (node (ref "Q26") (pin "B") (pinfunction "C_B") (pintype "passive"))
      (node (ref "R15") (pin "1") (pinfunction "1_1") (pintype "passive"))
      (node (ref "R5") (pin "1") (pinfunction "1_1") (pintype "passive"))
      (node (ref "R6") (pin "1") (pinfunction "1_1") (pintype "passive"))
      (node (ref "R9") (pin "1") (pinfunction "1_1") (pintype "passive"))
      (node (ref "TR3") (pin "1") (pinfunction "A_1") (pintype "passive"))
      (node (ref "U$1") (pin "P$11") (pinfunction "P$11_P$11") (pintype "bidirectional"))
      (node (ref "U$1") (pin "P$12") (pinfunction "P$12_P$12") (pintype "bidirectional"))
      (node (ref "U$1") (pin "P$29") (pinfunction "P$29_P$29") (pintype "bidirectional"))
      (node (ref "U$1") (pin "P$30") (pinfunction "P$30_P$30") (pintype "bidirectional"))
    )
    (net (code "52") (name "unconnected-(U$1-PadP$14)") (class "Default")
      (node (ref "U$1") (pin "P$14") (pinfunction "P$14_P$14") (pintype "bidirectional"))
    )
    (net (code "53") (name "unconnected-(U$1-PadP$15)") (class "Default")
      (node (ref "U$1") (pin "P$15") (pinfunction "P$15_P$15") (pintype "bidirectional"))
    )
    (net (code "54") (name "unconnected-(U$1-PadP$16)") (class "Default")
      (node (ref "U$1") (pin "P$16") (pinfunction "P$16_P$16") (pintype "bidirectional"))
    )
    (net (code "55") (name "unconnected-(U$1-PadP$17)") (class "Default")
      (node (ref "U$1") (pin "P$17") (pinfunction "P$17_P$17") (pintype "bidirectional"))
    )
    (net (code "56") (name "unconnected-(U$1-PadP$34)") (class "Default")
      (node (ref "U$1") (pin "P$34") (pinfunction "P$34_P$34") (pintype "bidirectional"))
    )
    (net (code "57") (name "unconnected-(U$1-PadP$35)") (class "Default")
      (node (ref "U$1") (pin "P$35") (pinfunction "P$35_P$35") (pintype "bidirectional"))
    )
    (net (code "58") (name "unconnected-(U$1-PadP$36)") (class "Default")
      (node (ref "U$1") (pin "P$36") (pinfunction "P$36_P$36") (pintype "bidirectional"))
    )
    (net (code "59") (name "unconnected-(U$1-PadP$37)") (class "Default")
      (node (ref "U$1") (pin "P$37") (pinfunction "P$37_P$37") (pintype "bidirectional"))
    )
  )
)
